# merkur-22m0.net
KiCad netlist of a schematic drawn in EAGLE
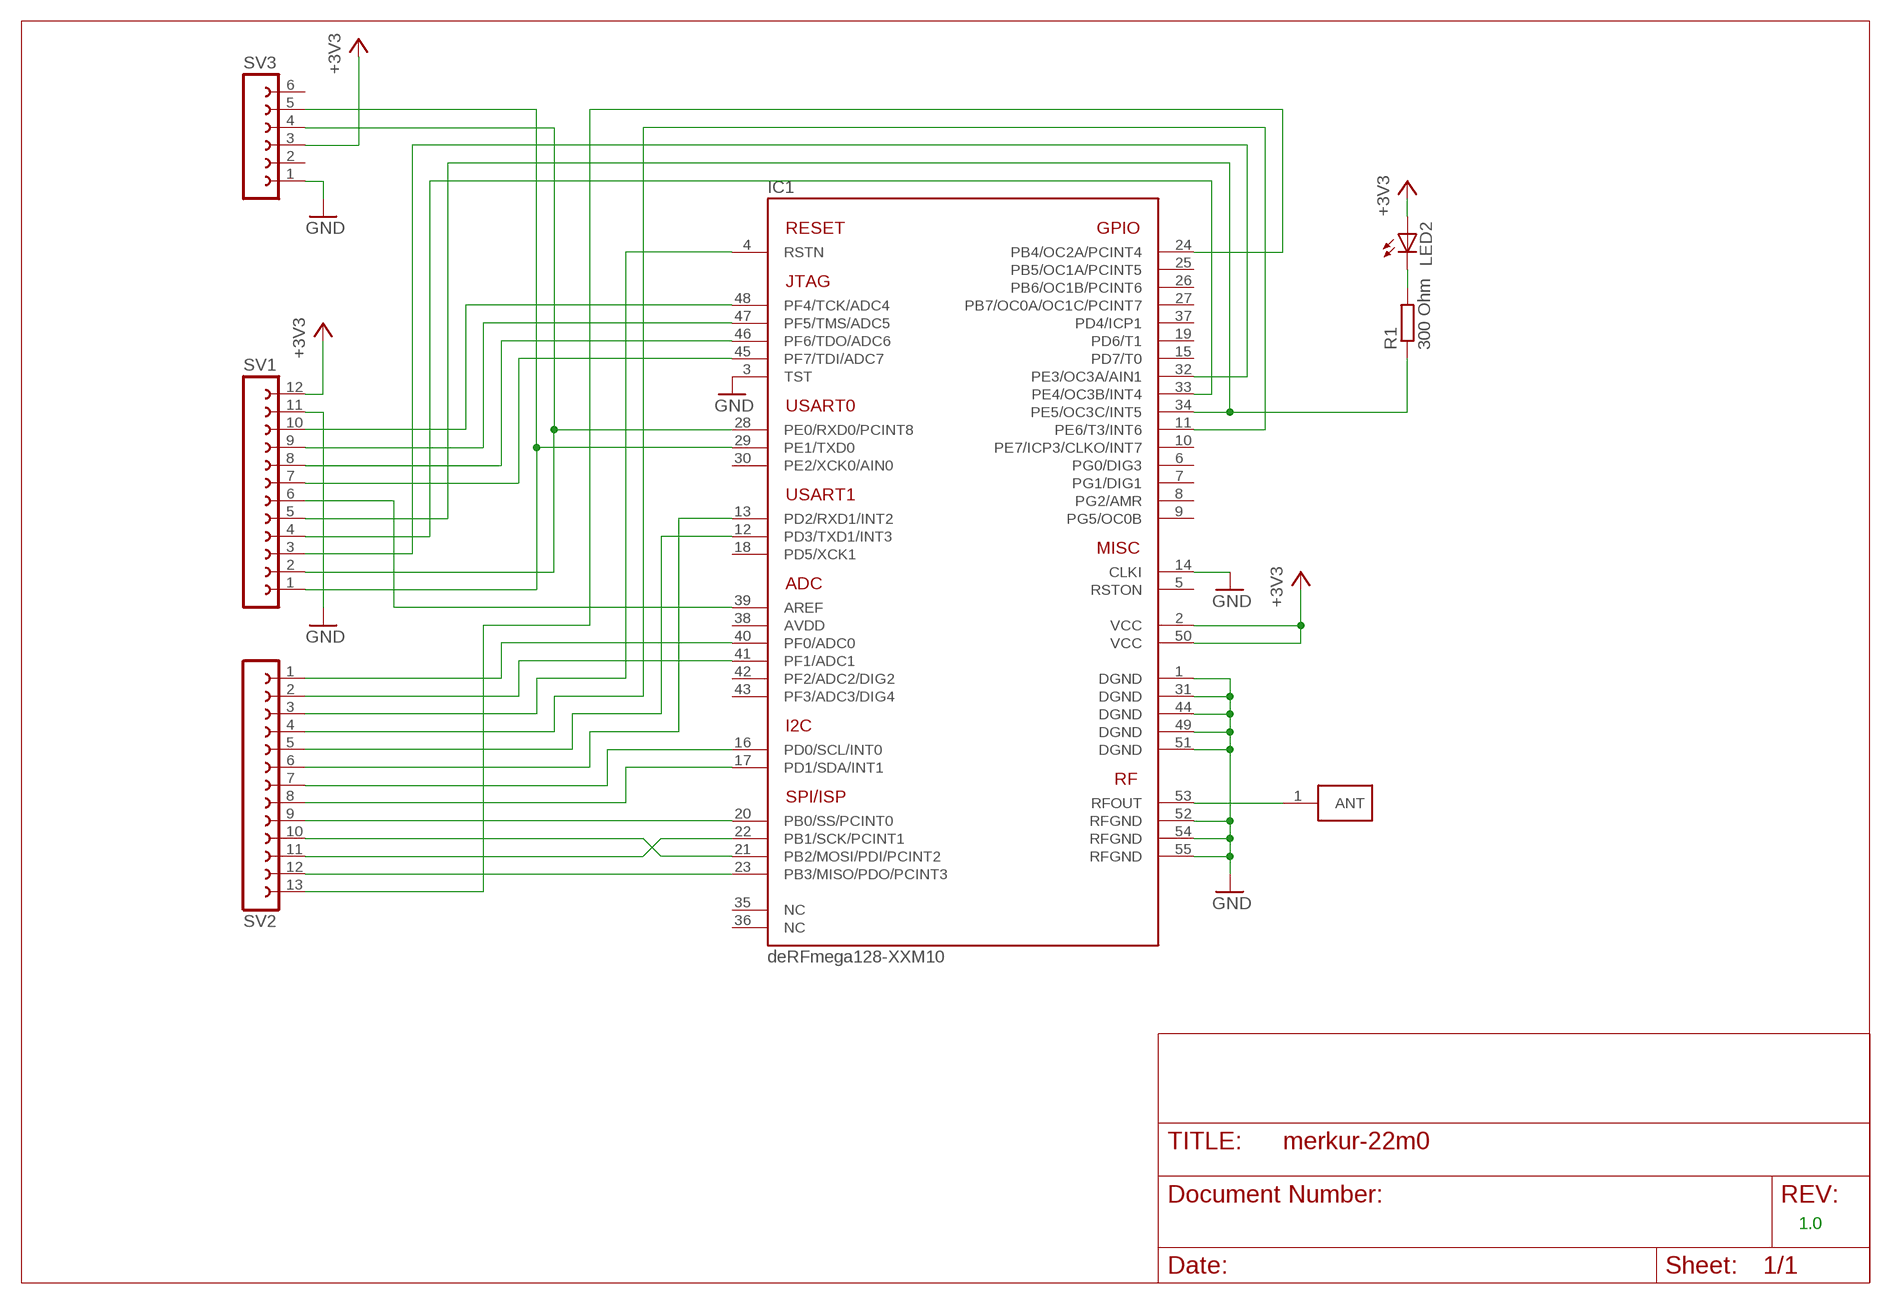
[diagram p0: schematic, sheet 1]

(export (version "E")
  (design (tool "Eeschema 10.0.6"))
  (components
    (comp (ref "IC1")
      (value "DERFMEGA128-XXM10")
      (footprint "eagle-import:A-M10")
      (libsource (lib "eagle-import") (part "DERFMEGA128-XXM10"))
    )
    (comp (ref "LED2")
      (value "LEDCHIP-LED0603")
      (footprint "eagle-import:CHIP-LED0603")
      (libsource (lib "eagle-import") (part "LEDCHIP-LED0603"))
    )
    (comp (ref "R1")
      (value "300 Ohm")
      (footprint "eagle-import:R0603")
      (libsource (lib "eagle-import") (part "R-EU_R0603"))
    )
    (comp (ref "SV1")
      (value "FE12-1")
      (footprint "eagle-import:FE12")
      (libsource (lib "eagle-import") (part "FE12-1"))
    )
    (comp (ref "SV2")
      (value "FE13-1")
      (footprint "eagle-import:FE13")
      (libsource (lib "eagle-import") (part "FE13-1"))
    )
    (comp (ref "SV3")
      (value "FE06-1")
      (footprint "eagle-import:FE06")
      (libsource (lib "eagle-import") (part "FE06-1"))
    )
    (comp (ref "U$1")
      (value "PAD")
      (footprint "eagle-import:FE05-1")
      (libsource (lib "eagle-import") (part "PAD"))
    )
  )
  (nets
    (net (code "1") (name "+3V3") (class "Default")
      (node (ref "IC1") (pin "2") (pinfunction "VCC_2") (pintype "power_in"))
      (node (ref "IC1") (pin "50") (pinfunction "VCC_50") (pintype "power_in"))
      (node (ref "LED2") (pin "A") (pinfunction "A_A") (pintype "passive"))
      (node (ref "SV1") (pin "12") (pinfunction "12_12") (pintype "passive"))
      (node (ref "SV3") (pin "3") (pinfunction "3_3") (pintype "passive"))
    )
    (net (code "2") (name "/AVDD") (class "Default")
      (node (ref "IC1") (pin "38") (pinfunction "AVDD_38") (pintype "power_in"))
    )
    (net (code "3") (name "GND") (class "Default")
      (node (ref "IC1") (pin "1") (pinfunction "DGND_1") (pintype "power_in"))
      (node (ref "IC1") (pin "14") (pinfunction "CLKI_14") (pintype "input"))
      (node (ref "IC1") (pin "3") (pinfunction "TST_3") (pintype "bidirectional"))
      (node (ref "IC1") (pin "31") (pinfunction "DGND_31") (pintype "power_in"))
      (node (ref "IC1") (pin "44") (pinfunction "DGND_44") (pintype "power_in"))
      (node (ref "IC1") (pin "49") (pinfunction "DGND_49") (pintype "power_in"))
      (node (ref "IC1") (pin "51") (pinfunction "DGND_51") (pintype "power_in"))
      (node (ref "IC1") (pin "52") (pinfunction "RFGND_52") (pintype "power_in"))
      (node (ref "IC1") (pin "54") (pinfunction "RFGND_54") (pintype "power_in"))
      (node (ref "IC1") (pin "55") (pinfunction "RFGND_55") (pintype "power_in"))
      (node (ref "SV1") (pin "11") (pinfunction "11_11") (pintype "passive"))
      (node (ref "SV3") (pin "1") (pinfunction "1_1") (pintype "passive"))
    )
    (net (code "4") (name "Net-(IC1-AREF)") (class "Default")
      (node (ref "IC1") (pin "39") (pinfunction "AREF_39") (pintype "bidirectional"))
      (node (ref "SV1") (pin "6") (pinfunction "6_6") (pintype "passive"))
    )
    (net (code "5") (name "Net-(IC1-PB0{slash}SS{slash}PCINT0)") (class "Default")
      (node (ref "IC1") (pin "20") (pinfunction "PB0/SS/PCINT0_20") (pintype "bidirectional"))
      (node (ref "SV2") (pin "9") (pinfunction "9_9") (pintype "passive"))
    )
    (net (code "6") (name "Net-(IC1-PB1{slash}SCK{slash}PCINT1)") (class "Default")
      (node (ref "IC1") (pin "22") (pinfunction "PB1/SCK/PCINT1_22") (pintype "bidirectional"))
      (node (ref "SV2") (pin "11") (pinfunction "11_11") (pintype "passive"))
    )
    (net (code "7") (name "Net-(IC1-PB2{slash}MOSI{slash}PDI{slash}PCINT2)") (class "Default")
      (node (ref "IC1") (pin "21") (pinfunction "PB2/MOSI/PDI/PCINT2_21") (pintype "bidirectional"))
      (node (ref "SV2") (pin "10") (pinfunction "10_10") (pintype "passive"))
    )
    (net (code "8") (name "Net-(IC1-PB3{slash}MISO{slash}PDO{slash}PCINT3)") (class "Default")
      (node (ref "IC1") (pin "23") (pinfunction "PB3/MISO/PDO/PCINT3_23") (pintype "bidirectional"))
      (node (ref "SV2") (pin "12") (pinfunction "12_12") (pintype "passive"))
    )
    (net (code "9") (name "Net-(IC1-PB4{slash}OC2A{slash}PCINT4)") (class "Default")
      (node (ref "IC1") (pin "24") (pinfunction "PB4/OC2A/PCINT4_24") (pintype "bidirectional"))
      (node (ref "SV2") (pin "13") (pinfunction "13_13") (pintype "passive"))
    )
    (net (code "10") (name "Net-(IC1-PD0{slash}SCL{slash}INT0)") (class "Default")
      (node (ref "IC1") (pin "16") (pinfunction "PD0/SCL/INT0_16") (pintype "bidirectional"))
      (node (ref "SV2") (pin "7") (pinfunction "7_7") (pintype "passive"))
    )
    (net (code "11") (name "Net-(IC1-PD1{slash}SDA{slash}INT1)") (class "Default")
      (node (ref "IC1") (pin "17") (pinfunction "PD1/SDA/INT1_17") (pintype "bidirectional"))
      (node (ref "SV2") (pin "8") (pinfunction "8_8") (pintype "passive"))
    )
    (net (code "12") (name "Net-(IC1-PD2{slash}RXD1{slash}INT2)") (class "Default")
      (node (ref "IC1") (pin "13") (pinfunction "PD2/RXD1/INT2_13") (pintype "bidirectional"))
      (node (ref "SV2") (pin "6") (pinfunction "6_6") (pintype "passive"))
    )
    (net (code "13") (name "Net-(IC1-PD3{slash}TXD1{slash}INT3)") (class "Default")
      (node (ref "IC1") (pin "12") (pinfunction "PD3/TXD1/INT3_12") (pintype "bidirectional"))
      (node (ref "SV2") (pin "5") (pinfunction "5_5") (pintype "passive"))
    )
    (net (code "14") (name "Net-(IC1-PE0{slash}RXD0{slash}PCINT8)") (class "Default")
      (node (ref "IC1") (pin "28") (pinfunction "PE0/RXD0/PCINT8_28") (pintype "bidirectional"))
      (node (ref "SV1") (pin "2") (pinfunction "2_2") (pintype "passive"))
      (node (ref "SV3") (pin "4") (pinfunction "4_4") (pintype "passive"))
    )
    (net (code "15") (name "Net-(IC1-PE1{slash}TXD0)") (class "Default")
      (node (ref "IC1") (pin "29") (pinfunction "PE1/TXD0_29") (pintype "bidirectional"))
      (node (ref "SV1") (pin "1") (pinfunction "1_1") (pintype "passive"))
      (node (ref "SV3") (pin "5") (pinfunction "5_5") (pintype "passive"))
    )
    (net (code "16") (name "Net-(IC1-PE3{slash}OC3A{slash}AIN1)") (class "Default")
      (node (ref "IC1") (pin "32") (pinfunction "PE3/OC3A/AIN1_32") (pintype "bidirectional"))
      (node (ref "SV1") (pin "3") (pinfunction "3_3") (pintype "passive"))
    )
    (net (code "17") (name "Net-(IC1-PE4{slash}OC3B{slash}INT4)") (class "Default")
      (node (ref "IC1") (pin "33") (pinfunction "PE4/OC3B/INT4_33") (pintype "bidirectional"))
      (node (ref "SV1") (pin "4") (pinfunction "4_4") (pintype "passive"))
    )
    (net (code "18") (name "Net-(IC1-PE5{slash}OC3C{slash}INT5)") (class "Default")
      (node (ref "IC1") (pin "34") (pinfunction "PE5/OC3C/INT5_34") (pintype "bidirectional"))
      (node (ref "R1") (pin "1") (pinfunction "1_1") (pintype "passive"))
      (node (ref "SV1") (pin "5") (pinfunction "5_5") (pintype "passive"))
    )
    (net (code "19") (name "Net-(IC1-PE6{slash}T3{slash}INT6)") (class "Default")
      (node (ref "IC1") (pin "11") (pinfunction "PE6/T3/INT6_11") (pintype "bidirectional"))
      (node (ref "SV2") (pin "4") (pinfunction "4_4") (pintype "passive"))
    )
    (net (code "20") (name "Net-(IC1-PF0{slash}ADC0)") (class "Default")
      (node (ref "IC1") (pin "40") (pinfunction "PF0/ADC0_40") (pintype "bidirectional"))
      (node (ref "SV2") (pin "1") (pinfunction "1_1") (pintype "passive"))
    )
    (net (code "21") (name "Net-(IC1-PF1{slash}ADC1)") (class "Default")
      (node (ref "IC1") (pin "41") (pinfunction "PF1/ADC1_41") (pintype "bidirectional"))
      (node (ref "SV2") (pin "2") (pinfunction "2_2") (pintype "passive"))
    )
    (net (code "22") (name "Net-(IC1-PF4{slash}TCK{slash}ADC4)") (class "Default")
      (node (ref "IC1") (pin "48") (pinfunction "PF4/TCK/ADC4_48") (pintype "bidirectional"))
      (node (ref "SV1") (pin "10") (pinfunction "10_10") (pintype "passive"))
    )
    (net (code "23") (name "Net-(IC1-PF5{slash}TMS{slash}ADC5)") (class "Default")
      (node (ref "IC1") (pin "47") (pinfunction "PF5/TMS/ADC5_47") (pintype "bidirectional"))
      (node (ref "SV1") (pin "9") (pinfunction "9_9") (pintype "passive"))
    )
    (net (code "24") (name "Net-(IC1-PF6{slash}TDO{slash}ADC6)") (class "Default")
      (node (ref "IC1") (pin "46") (pinfunction "PF6/TDO/ADC6_46") (pintype "bidirectional"))
      (node (ref "SV1") (pin "8") (pinfunction "8_8") (pintype "passive"))
    )
    (net (code "25") (name "Net-(IC1-PF7{slash}TDI{slash}ADC7)") (class "Default")
      (node (ref "IC1") (pin "45") (pinfunction "PF7/TDI/ADC7_45") (pintype "bidirectional"))
      (node (ref "SV1") (pin "7") (pinfunction "7_7") (pintype "passive"))
    )
    (net (code "26") (name "Net-(IC1-RFOUT)") (class "Default")
      (node (ref "IC1") (pin "53") (pinfunction "RFOUT_53") (pintype "power_in"))
      (node (ref "U$1") (pin "1") (pinfunction "ANT_1") (pintype "output"))
    )
    (net (code "27") (name "Net-(IC1-RSTN)") (class "Default")
      (node (ref "IC1") (pin "4") (pinfunction "RSTN_4") (pintype "input"))
      (node (ref "SV2") (pin "3") (pinfunction "3_3") (pintype "passive"))
    )
    (net (code "28") (name "Net-(LED2-PadC)") (class "Default")
      (node (ref "LED2") (pin "C") (pinfunction "C_C") (pintype "passive"))
      (node (ref "R1") (pin "2") (pinfunction "2_2") (pintype "passive"))
    )
    (net (code "29") (name "unconnected-(IC1-NC-Pad35)") (class "Default")
      (node (ref "IC1") (pin "35") (pinfunction "NC_35") (pintype "no_connect"))
    )
    (net (code "30") (name "unconnected-(IC1-NC-Pad36)") (class "Default")
      (node (ref "IC1") (pin "36") (pinfunction "NC_36") (pintype "no_connect"))
    )
    (net (code "31") (name "unconnected-(IC1-PB5{slash}OC1A{slash}PCINT5-Pad25)") (class "Default")
      (node (ref "IC1") (pin "25") (pinfunction "PB5/OC1A/PCINT5_25") (pintype "bidirectional"))
    )
    (net (code "32") (name "unconnected-(IC1-PB6{slash}OC1B{slash}PCINT6-Pad26)") (class "Default")
      (node (ref "IC1") (pin "26") (pinfunction "PB6/OC1B/PCINT6_26") (pintype "bidirectional"))
    )
    (net (code "33") (name "unconnected-(IC1-PB7{slash}OC0A{slash}OC1C{slash}PCINT7-Pad27)") (class "Default")
      (node (ref "IC1") (pin "27") (pinfunction "PB7/OC0A/OC1C/PCINT7_27") (pintype "bidirectional"))
    )
    (net (code "34") (name "unconnected-(IC1-PD4{slash}ICP1-Pad37)") (class "Default")
      (node (ref "IC1") (pin "37") (pinfunction "PD4/ICP1_37") (pintype "bidirectional"))
    )
    (net (code "35") (name "unconnected-(IC1-PD5{slash}XCK1-Pad18)") (class "Default")
      (node (ref "IC1") (pin "18") (pinfunction "PD5/XCK1_18") (pintype "bidirectional"))
    )
    (net (code "36") (name "unconnected-(IC1-PD6{slash}T1-Pad19)") (class "Default")
      (node (ref "IC1") (pin "19") (pinfunction "PD6/T1_19") (pintype "bidirectional"))
    )
    (net (code "37") (name "unconnected-(IC1-PD7{slash}T0-Pad15)") (class "Default")
      (node (ref "IC1") (pin "15") (pinfunction "PD7/T0_15") (pintype "bidirectional"))
    )
    (net (code "38") (name "unconnected-(IC1-PE2{slash}XCK0{slash}AIN0-Pad30)") (class "Default")
      (node (ref "IC1") (pin "30") (pinfunction "PE2/XCK0/AIN0_30") (pintype "bidirectional"))
    )
    (net (code "39") (name "unconnected-(IC1-PE7{slash}ICP3{slash}CLKO{slash}INT7-Pad10)") (class "Default")
      (node (ref "IC1") (pin "10") (pinfunction "PE7/ICP3/CLKO/INT7_10") (pintype "bidirectional"))
    )
    (net (code "40") (name "unconnected-(IC1-PF2{slash}ADC2{slash}DIG2-Pad42)") (class "Default")
      (node (ref "IC1") (pin "42") (pinfunction "PF2/ADC2/DIG2_42") (pintype "bidirectional"))
    )
    (net (code "41") (name "unconnected-(IC1-PF3{slash}ADC3{slash}DIG4-Pad43)") (class "Default")
      (node (ref "IC1") (pin "43") (pinfunction "PF3/ADC3/DIG4_43") (pintype "bidirectional"))
    )
    (net (code "42") (name "unconnected-(IC1-PG0{slash}DIG3-Pad6)") (class "Default")
      (node (ref "IC1") (pin "6") (pinfunction "PG0/DIG3_6") (pintype "bidirectional"))
    )
    (net (code "43") (name "unconnected-(IC1-PG1{slash}DIG1-Pad7)") (class "Default")
      (node (ref "IC1") (pin "7") (pinfunction "PG1/DIG1_7") (pintype "bidirectional"))
    )
    (net (code "44") (name "unconnected-(IC1-PG2{slash}AMR-Pad8)") (class "Default")
      (node (ref "IC1") (pin "8") (pinfunction "PG2/AMR_8") (pintype "bidirectional"))
    )
    (net (code "45") (name "unconnected-(IC1-PG5{slash}OC0B-Pad9)") (class "Default")
      (node (ref "IC1") (pin "9") (pinfunction "PG5/OC0B_9") (pintype "bidirectional"))
    )
    (net (code "46") (name "unconnected-(IC1-RSTON-Pad5)") (class "Default")
      (node (ref "IC1") (pin "5") (pinfunction "RSTON_5") (pintype "output"))
    )
    (net (code "47") (name "unconnected-(SV3-Pad2)") (class "Default")
      (node (ref "SV3") (pin "2") (pinfunction "2_2") (pintype "passive"))
    )
    (net (code "48") (name "unconnected-(SV3-Pad6)") (class "Default")
      (node (ref "SV3") (pin "6") (pinfunction "6_6") (pintype "passive"))
    )
  )
)
